# INPUT_LOGIC.net
KiCad netlist of a schematic drawn in Altium Designer
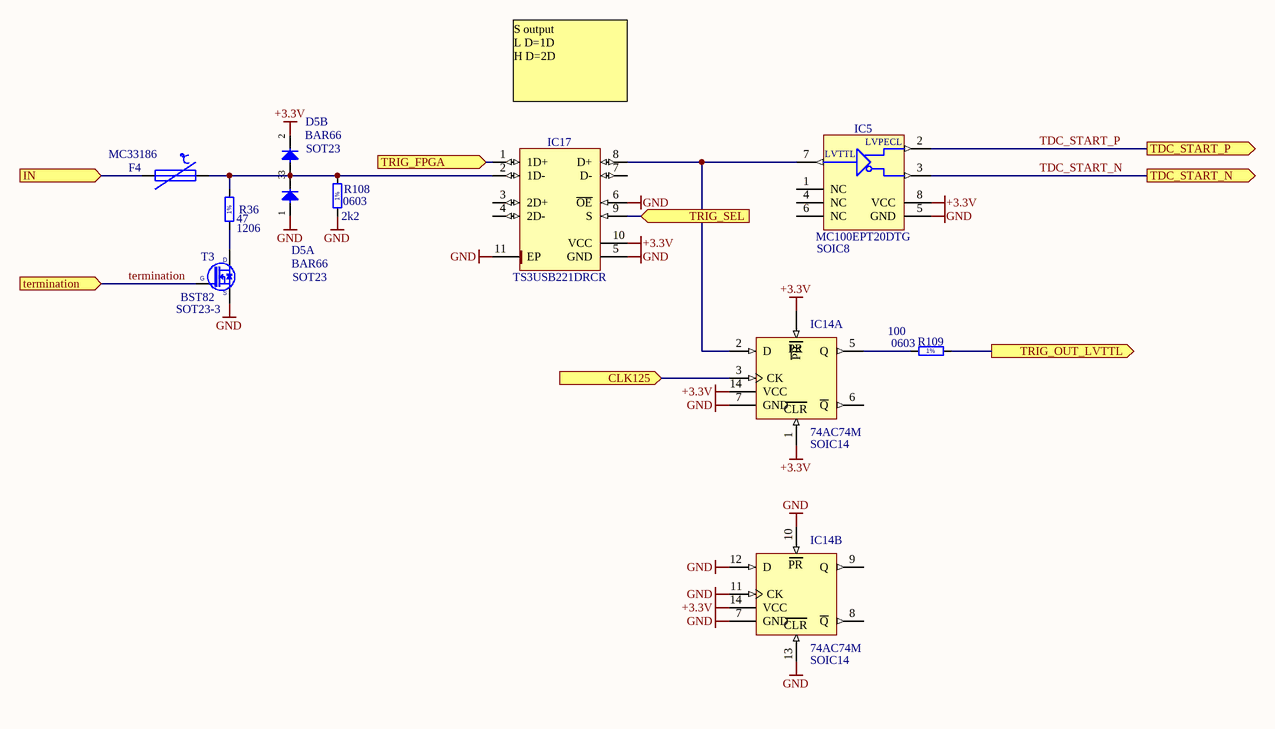
[diagram p0: INPUT_LOGIC.SchDoc]

(export (version "E")
  (design (tool "Eeschema 10.0.6"))
  (components
    (comp (ref "D5")
      (value "BAR66")
      (footprint "SOT95P240X110-3N")
      (description "Serial Diode")
      (fields
        (field (name "VOLTAGE") "150V")
        (field (name "POWER") "250mA")
        (field (name "CASE") "SOT23")
        (field (name "AUTHOR") "CERN DEM JLC")
      )
      (libsource (lib "ICs And Semiconductors") (part "Diode x2 A1C3_A3C2"))
    )
    (comp (ref "F4")
      (value "MC33186")
      (footprint "PTC_MC33186")
      (description "polymer FUSE Multicomp (Farnell)")
      (libsource (lib "LIBRARY_SCH") (part "F_POLYSWITCH_0.1A"))
    )
    (comp (ref "IC5")
      (value "MC100EPT20DTG")
      (footprint "SOP65P490X110-8N")
      (description "3.3V LVTTL/LVCMOS to Differential LVPECL Translator")
      (fields
        (field (name "MANUFACTURER") "ON SEMICONDUCTOR")
        (field (name "CASE") "SOIC8")
        (field (name "AUTHOR") "CERN DEM JLC")
      )
      (libsource (lib "ICs And Semiconductors") (part "10EPT20D"))
    )
    (comp (ref "IC14")
      (value "74AC74M")
      (footprint "SOIC127P600X175-14N")
      (description "Dual D-Type Flip Flop with Preset and Clear")
      (fields
        (field (name "MANUFACTURER") "ST MICROELECTRONICS")
        (field (name "CASE") "SOIC14")
        (field (name "AUTHOR") "CERN DEM JMW")
      )
      (libsource (lib "ICs And Semiconductors") (part "7474"))
    )
    (comp (ref "IC17")
      (value "TS3USB221DRCR")
      (footprint "SON50P300X300X100-11N-R175X250")
      (description "High-Speed USB 2.0 (480-Mbps) 1:2 Multiplexer/Demultiplexer Switch With Single Enable")
      (fields (field (name "MANUFACTURER") "TEXAS INSTRUMENTS") (field (name "AUTHOR") "CERN DEM JLC"))
      (libsource (lib "ICs And Semiconductors") (part "TS3USB221DRC"))
    )
    (comp (ref "R36")
      (value "47")
      (footprint "RESC3216X65N")
      (description "Resistor - 1%")
      (fields
        (field (name "PART NUMBER") "R1206_47R_1%_0.25W_100PPM")
        (field (name "POWER") "0.25W")
        (field (name "CASE") "1206")
        (field (name "AUTHOR") "CERN DEM JLC")
      )
      (libsource (lib "Resistors") (part "Resistor - 1%"))
    )
    (comp (ref "R108")
      (value "2k2")
      (footprint "RESC1608X55N")
      (description "Resistor - 1%")
      (fields
        (field (name "PART NUMBER") "R0603_2K2_1%_0.1W_100PPM")
        (field (name "POWER") "0.1W")
        (field (name "CASE") "0603")
        (field (name "AUTHOR") "CERN DEM JLC")
      )
      (libsource (lib "Resistors") (part "Resistor - 1%"))
    )
    (comp (ref "R109")
      (value "100")
      (footprint "RESC1608X55N")
      (description "Resistor - 1%")
      (fields
        (field (name "PART NUMBER") "R0603_100R_1%_0.1W_100PPM")
        (field (name "POWER") "0.1W")
        (field (name "CASE") "0603")
        (field (name "AUTHOR") "CERN DEM JLC")
      )
      (libsource (lib "Resistors") (part "Resistor - 1%"))
    )
    (comp (ref "T3")
      (value "BST82")
      (footprint "SOT95P240X110-3N")
      (description "N-CHANNEL MOSFET WITH DIODE")
      (fields
        (field (name "MANUFACTURER") "NXP SEMICONDUCTORS")
        (field (name "CASE") "SOT23-3")
        (field (name "AUTHOR") "CERN DEM JLC")
      )
      (libsource (lib "ICs And Semiconductors") (part "N-MOSFET-D 1G 2S 3D"))
    )
  )
  (nets
    (net (code "1") (name "+3.3V") (class "Default")
      (node (ref "D5") (pin "2") (pinfunction "C_2") (pintype "passive"))
      (node (ref "IC14") (pin "1") (pinfunction "~{CLR}_1") (pintype "input"))
      (node (ref "IC14") (pin "14") (pinfunction "VCC_14") (pintype "power_in"))
      (node (ref "IC14") (pin "4") (pinfunction "~{PR}_4") (pintype "input"))
      (node (ref "IC17") (pin "10") (pinfunction "VCC_10") (pintype "power_in"))
      (node (ref "IC5") (pin "8") (pinfunction "VCC_8") (pintype "power_in"))
    )
    (net (code "2") (name "/CLK125") (class "Default")
      (node (ref "IC14") (pin "3") (pinfunction "CK_3") (pintype "input"))
    )
    (net (code "3") (name "/IN") (class "Default")
      (node (ref "F4") (pin "1") (pinfunction "1_1") (pintype "passive"))
    )
    (net (code "4") (name "/TDC_START_N") (class "Default")
      (node (ref "IC5") (pin "3") (pinfunction "~{Q}_3") (pintype "output"))
    )
    (net (code "5") (name "/TDC_START_P") (class "Default")
      (node (ref "IC5") (pin "2") (pinfunction "Q_2") (pintype "output"))
    )
    (net (code "6") (name "/TRIG_FPGA") (class "Default")
      (node (ref "IC17") (pin "1") (pinfunction "1D+_1") (pintype "bidirectional"))
    )
    (net (code "7") (name "/TRIG_OUT_LVTTL") (class "Default")
      (node (ref "R109") (pin "2") (pinfunction "2_2") (pintype "passive"))
    )
    (net (code "8") (name "/TRIG_SEL") (class "Default")
      (node (ref "IC17") (pin "9") (pinfunction "S_9") (pintype "input"))
    )
    (net (code "9") (name "/termination") (class "Default")
      (node (ref "T3") (pin "1") (pinfunction "G_1") (pintype "passive"))
    )
    (net (code "10") (name "GND") (class "Default")
      (node (ref "D5") (pin "1") (pinfunction "A_1") (pintype "passive"))
      (node (ref "IC14") (pin "10") (pinfunction "~{PR}_10") (pintype "input"))
      (node (ref "IC14") (pin "11") (pinfunction "CK_11") (pintype "input"))
      (node (ref "IC14") (pin "12") (pinfunction "D_12") (pintype "input"))
      (node (ref "IC14") (pin "13") (pinfunction "~{CLR}_13") (pintype "input"))
      (node (ref "IC14") (pin "7") (pinfunction "GND_7") (pintype "power_in"))
      (node (ref "IC17") (pin "11") (pinfunction "EP_11") (pintype "power_in"))
      (node (ref "IC17") (pin "5") (pinfunction "GND_5") (pintype "power_in"))
      (node (ref "IC17") (pin "6") (pinfunction "~{OE}_6") (pintype "input"))
      (node (ref "IC5") (pin "5") (pinfunction "GND_5") (pintype "power_in"))
      (node (ref "R108") (pin "1") (pinfunction "1_1") (pintype "passive"))
      (node (ref "T3") (pin "2") (pinfunction "S_2") (pintype "passive"))
    )
    (net (code "11") (name "Net-(D5A-COMAC)") (class "Default")
      (node (ref "D5") (pin "3") (pinfunction "COMAC_3") (pintype "passive"))
      (node (ref "F4") (pin "2") (pinfunction "2_2") (pintype "passive"))
      (node (ref "IC17") (pin "2") (pinfunction "1D-_2") (pintype "bidirectional"))
      (node (ref "R108") (pin "2") (pinfunction "2_2") (pintype "passive"))
      (node (ref "R36") (pin "2") (pinfunction "2_2") (pintype "passive"))
    )
    (net (code "12") (name "Net-(IC14A-D)") (class "Default")
      (node (ref "IC14") (pin "2") (pinfunction "D_2") (pintype "input"))
      (node (ref "IC17") (pin "8") (pinfunction "D+_8") (pintype "bidirectional"))
      (node (ref "IC5") (pin "7") (pinfunction "D_7") (pintype "output"))
    )
    (net (code "13") (name "Net-(IC14A-Q)") (class "Default")
      (node (ref "IC14") (pin "5") (pinfunction "Q_5") (pintype "output"))
      (node (ref "R109") (pin "1") (pinfunction "1_1") (pintype "passive"))
    )
    (net (code "14") (name "Net-(T3-D)") (class "Default")
      (node (ref "R36") (pin "1") (pinfunction "1_1") (pintype "passive"))
      (node (ref "T3") (pin "3") (pinfunction "D_3") (pintype "passive"))
    )
    (net (code "15") (name "unconnected-(IC5-NC-Pad1)") (class "Default")
      (node (ref "IC5") (pin "1") (pinfunction "NC_1") (pintype "passive"))
    )
    (net (code "16") (name "unconnected-(IC5-NC-Pad4)") (class "Default")
      (node (ref "IC5") (pin "4") (pinfunction "NC_4") (pintype "passive"))
    )
    (net (code "17") (name "unconnected-(IC5-NC-Pad6)") (class "Default")
      (node (ref "IC5") (pin "6") (pinfunction "NC_6") (pintype "passive"))
    )
    (net (code "18") (name "unconnected-(IC14A-~{Q}-Pad6)") (class "Default")
      (node (ref "IC14") (pin "6") (pinfunction "~{Q}_6") (pintype "output"))
    )
    (net (code "19") (name "unconnected-(IC14B-Q-Pad9)") (class "Default")
      (node (ref "IC14") (pin "9") (pinfunction "Q_9") (pintype "output"))
    )
    (net (code "20") (name "unconnected-(IC14B-~{Q}-Pad8)") (class "Default")
      (node (ref "IC14") (pin "8") (pinfunction "~{Q}_8") (pintype "output"))
    )
    (net (code "21") (name "unconnected-(IC17-2D+-Pad3)") (class "Default")
      (node (ref "IC17") (pin "3") (pinfunction "2D+_3") (pintype "bidirectional"))
    )
    (net (code "22") (name "unconnected-(IC17-2D--Pad4)") (class "Default")
      (node (ref "IC17") (pin "4") (pinfunction "2D-_4") (pintype "bidirectional"))
    )
    (net (code "23") (name "unconnected-(IC17-D--Pad7)") (class "Default")
      (node (ref "IC17") (pin "7") (pinfunction "D-_7") (pintype "bidirectional"))
    )
  )
)
